# ATMega328.net
KiCad netlist of a schematic drawn in Altium Designer
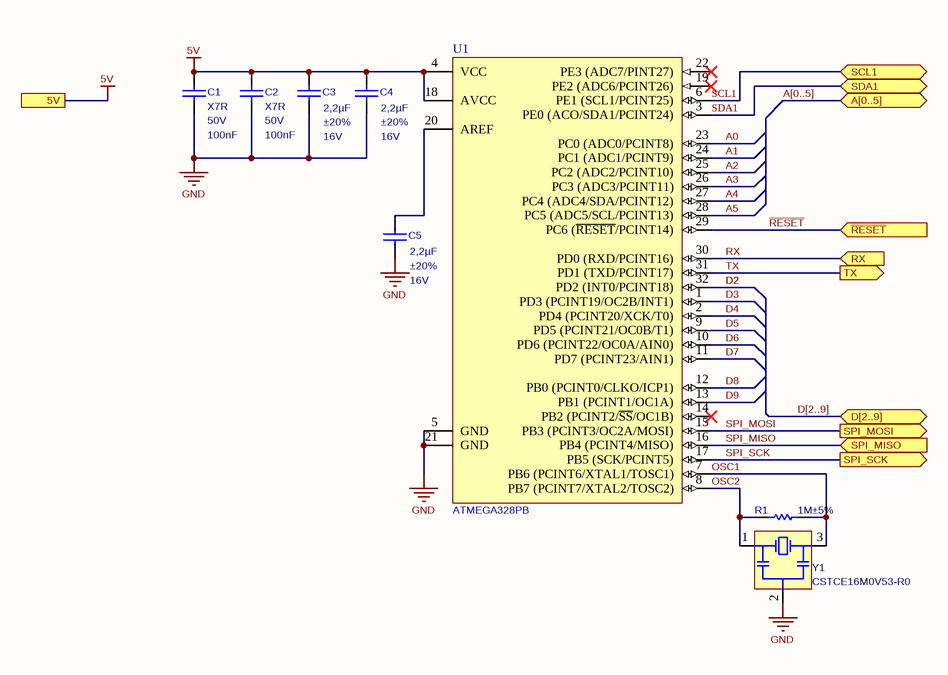
[diagram p0: ATMega328.SchDoc]

(export (version "E")
  (design (tool "Eeschema 10.0.6"))
  (components
    (comp (ref "C1")
      (value "C0603_100nF_50V_±10%_X7R")
      (footprint "C0603")
      (fields
        (field (name "DIELECTRIC") "X7R")
        (field (name "VOLTAGE") "50V")
        (field (name "CAPACITANCE") "100nF")
        (field (name "MANUFACTURER") "Kemet")
        (field (name "TOLERANCE") "±10%")
      )
      (libsource (lib "BQ Vault") (part "CMP-00257-1"))
    )
    (comp (ref "C2")
      (value "C0603_100nF_50V_±10%_X7R")
      (footprint "C0603")
      (fields
        (field (name "DIELECTRIC") "X7R")
        (field (name "VOLTAGE") "50V")
        (field (name "CAPACITANCE") "100nF")
        (field (name "MANUFACTURER") "Kemet")
        (field (name "TOLERANCE") "±10%")
      )
      (libsource (lib "BQ Vault") (part "CMP-00257-1"))
    )
    (comp (ref "C3")
      (value "C0402_2.2uF_16V_±20%")
      (footprint "C0402")
      (description "C0402_2.2uF_16V_±20%_X5R")
      (fields
        (field (name "VOLTAGE") "16V")
        (field (name "CAPACITANCE") "2,2µF")
        (field (name "PART NUMBER") "C0402_2.2uF_16V_±10%")
        (field (name "TOLERANCE") "±20%")
        (field (name "MANUFACTURER") "TDK")
      )
      (libsource (lib "BQ Vault") (part "Capacitor"))
    )
    (comp (ref "C4")
      (value "C0402_2.2uF_16V_±20%")
      (footprint "C0402")
      (description "C0402_2.2uF_16V_±20%_X5R")
      (fields
        (field (name "VOLTAGE") "16V")
        (field (name "CAPACITANCE") "2,2µF")
        (field (name "PART NUMBER") "C0402_2.2uF_16V_±10%")
        (field (name "TOLERANCE") "±20%")
        (field (name "MANUFACTURER") "TDK")
      )
      (libsource (lib "BQ Vault") (part "Capacitor"))
    )
    (comp (ref "C5")
      (value "C0402_2.2uF_16V_±20%")
      (footprint "C0402")
      (description "C0402_2.2uF_16V_±20%_X5R")
      (fields
        (field (name "VOLTAGE") "16V")
        (field (name "CAPACITANCE") "2,2µF")
        (field (name "PART NUMBER") "C0402_2.2uF_16V_±10%")
        (field (name "TOLERANCE") "±20%")
        (field (name "MANUFACTURER") "TDK")
      )
      (libsource (lib "BQ Vault") (part "Capacitor"))
    )
    (comp (ref "R1")
      (value "R0603_1M_0.1W_±5%")
      (footprint "R0603")
      (fields
        (field (name "TOLERANCE") "±5%")
        (field (name "POWER") "0.1W")
        (field (name "RESISTANCE") "1M")
        (field (name "MANUFACTURER") "Vishay")
      )
      (libsource (lib "BQ Vault") (part "Resistor"))
    )
    (comp (ref "U1")
      (value "ATMEGA328PB")
      (footprint "TQFP32")
      (description "8-bit Microcontrollers - MCU 32KB In-system Flash 20MHz 1.8V-5.5V")
      (fields (field (name "MANUFACTURER") "Atmel"))
      (libsource (lib "BQ Vault") (part "ATMEGA328PB"))
    )
    (comp (ref "Y1")
      (value "CSTCE16M0V53-R0")
      (footprint "Resonator_1.3x3.2")
      (description "Resonator 16MHz")
      (fields (field (name "MANUFACTURER") "Murata"))
      (libsource (lib "BQ Vault") (part "Resonator 3 pin"))
    )
  )
  (nets
    (net (code "1") (name "/A0") (class "Default")
      (node (ref "U1") (pin "23") (pinfunction "PC0_(ADC0/PCINT8)_23") (pintype "bidirectional"))
    )
    (net (code "2") (name "/A1") (class "Default")
      (node (ref "U1") (pin "24") (pinfunction "PC1_(ADC1/PCINT9)_24") (pintype "bidirectional"))
    )
    (net (code "3") (name "/A2") (class "Default")
      (node (ref "U1") (pin "25") (pinfunction "PC2_(ADC2/PCINT10)_25") (pintype "bidirectional"))
    )
    (net (code "4") (name "/A3") (class "Default")
      (node (ref "U1") (pin "26") (pinfunction "PC3_(ADC3/PCINT11)_26") (pintype "bidirectional"))
    )
    (net (code "5") (name "/A4") (class "Default")
      (node (ref "U1") (pin "27") (pinfunction "PC4_(ADC4/SDA/PCINT12)_27") (pintype "bidirectional"))
    )
    (net (code "6") (name "/A5") (class "Default")
      (node (ref "U1") (pin "28") (pinfunction "PC5_(ADC5/SCL/PCINT13)_28") (pintype "bidirectional"))
    )
    (net (code "8") (name "/D2") (class "Default")
      (node (ref "U1") (pin "32") (pinfunction "PD2_(INT0/PCINT18)_32") (pintype "bidirectional"))
    )
    (net (code "9") (name "/D3") (class "Default")
      (node (ref "U1") (pin "1") (pinfunction "PD3_(PCINT19/OC2B/INT1)_1") (pintype "bidirectional"))
    )
    (net (code "10") (name "/D4") (class "Default")
      (node (ref "U1") (pin "2") (pinfunction "PD4_(PCINT20/XCK/T0)_2") (pintype "bidirectional"))
    )
    (net (code "11") (name "/D5") (class "Default")
      (node (ref "U1") (pin "9") (pinfunction "PD5_(PCINT21/OC0B/T1)_9") (pintype "bidirectional"))
    )
    (net (code "12") (name "/D6") (class "Default")
      (node (ref "U1") (pin "10") (pinfunction "PD6_(PCINT22/OC0A/AIN0)_10") (pintype "bidirectional"))
    )
    (net (code "13") (name "/D7") (class "Default")
      (node (ref "U1") (pin "11") (pinfunction "PD7_(PCINT23/AIN1)_11") (pintype "bidirectional"))
    )
    (net (code "14") (name "/D8") (class "Default")
      (node (ref "U1") (pin "12") (pinfunction "PB0_(PCINT0/CLKO/ICP1)_12") (pintype "bidirectional"))
    )
    (net (code "15") (name "/D9") (class "Default")
      (node (ref "U1") (pin "13") (pinfunction "PB1_(PCINT1/OC1A)_13") (pintype "bidirectional"))
    )
    (net (code "17") (name "/OSC1") (class "Default")
      (node (ref "R1") (pin "1") (pinfunction "1_1") (pintype "passive"))
      (node (ref "U1") (pin "7") (pinfunction "PB6_(PCINT6/XTAL1/TOSC1)_7") (pintype "bidirectional"))
      (node (ref "Y1") (pin "3") (pinfunction "OSC2_3") (pintype "passive"))
    )
    (net (code "18") (name "/OSC2") (class "Default")
      (node (ref "R1") (pin "2") (pinfunction "2_2") (pintype "passive"))
      (node (ref "U1") (pin "8") (pinfunction "PB7_(PCINT7/XTAL2/TOSC2)_8") (pintype "bidirectional"))
      (node (ref "Y1") (pin "1") (pinfunction "OSC1_1") (pintype "passive"))
    )
    (net (code "19") (name "/RX") (class "Default")
      (node (ref "U1") (pin "30") (pinfunction "PD0_(RXD/PCINT16)_30") (pintype "bidirectional"))
    )
    (net (code "20") (name "/SCL1") (class "Default")
      (node (ref "U1") (pin "6") (pinfunction "PE1_(SCL1/PCINT25)_6") (pintype "bidirectional"))
    )
    (net (code "21") (name "/SDA1") (class "Default")
      (node (ref "U1") (pin "3") (pinfunction "PE0_(ACO/SDA1/PCINT24)_3") (pintype "bidirectional"))
    )
    (net (code "22") (name "/SPI_MISO") (class "Default")
      (node (ref "U1") (pin "16") (pinfunction "PB4_(PCINT4/MISO)_16") (pintype "bidirectional"))
    )
    (net (code "23") (name "/SPI_MOSI") (class "Default")
      (node (ref "U1") (pin "15") (pinfunction "PB3_(PCINT3/OC2A/MOSI)_15") (pintype "bidirectional"))
    )
    (net (code "24") (name "/SPI_SCK") (class "Default")
      (node (ref "U1") (pin "17") (pinfunction "PB5_(SCK/PCINT5)_17") (pintype "bidirectional"))
    )
    (net (code "25") (name "/TX") (class "Default")
      (node (ref "U1") (pin "31") (pinfunction "PD1_(TXD/PCINT17)_31") (pintype "bidirectional"))
    )
    (net (code "26") (name "/~{RESET}") (class "Default")
      (node (ref "U1") (pin "29") (pinfunction "PC6_(~{RESET}/PCINT14)_29") (pintype "bidirectional"))
    )
    (net (code "27") (name "5V") (class "Default")
      (node (ref "C1") (pin "2") (pinfunction "2_2") (pintype "passive"))
      (node (ref "C2") (pin "2") (pinfunction "2_2") (pintype "passive"))
      (node (ref "C3") (pin "2") (pinfunction "2_2") (pintype "passive"))
      (node (ref "C4") (pin "2") (pinfunction "2_2") (pintype "passive"))
      (node (ref "U1") (pin "18") (pinfunction "AVCC_18") (pintype "power_in"))
      (node (ref "U1") (pin "4") (pinfunction "VCC_4") (pintype "power_in"))
    )
    (net (code "28") (name "GND") (class "Default")
      (node (ref "C1") (pin "1") (pinfunction "1_1") (pintype "passive"))
      (node (ref "C2") (pin "1") (pinfunction "1_1") (pintype "passive"))
      (node (ref "C3") (pin "1") (pinfunction "1_1") (pintype "passive"))
      (node (ref "C4") (pin "1") (pinfunction "1_1") (pintype "passive"))
      (node (ref "C5") (pin "1") (pinfunction "1_1") (pintype "passive"))
      (node (ref "U1") (pin "21") (pinfunction "GND_21") (pintype "power_in"))
      (node (ref "U1") (pin "5") (pinfunction "GND_5") (pintype "power_in"))
      (node (ref "Y1") (pin "2") (pinfunction "GND_2") (pintype "passive"))
    )
    (net (code "29") (name "Net-(U1-AREF)") (class "Default")
      (node (ref "C5") (pin "2") (pinfunction "2_2") (pintype "passive"))
      (node (ref "U1") (pin "20") (pinfunction "AREF_20") (pintype "passive"))
    )
    (net (code "30") (name "unconnected-(U1-PB2_(PCINT2{slash}~{SS}{slash}OC1B)-Pad14)") (class "Default")
      (node (ref "U1") (pin "14") (pinfunction "PB2_(PCINT2/~{SS}/OC1B)_14") (pintype "bidirectional+no_connect"))
    )
    (net (code "31") (name "unconnected-(U1-PE2_(ADC6{slash}PCINT26)-Pad19)") (class "Default")
      (node (ref "U1") (pin "19") (pinfunction "PE2_(ADC6/PCINT26)_19") (pintype "input+no_connect"))
    )
    (net (code "32") (name "unconnected-(U1-PE3_(ADC7{slash}PINT27)-Pad22)") (class "Default")
      (node (ref "U1") (pin "22") (pinfunction "PE3_(ADC7/PINT27)_22") (pintype "input+no_connect"))
    )
  )
)
